# MB_rpi_sys.net
KiCad netlist of a schematic drawn in Altium Designer
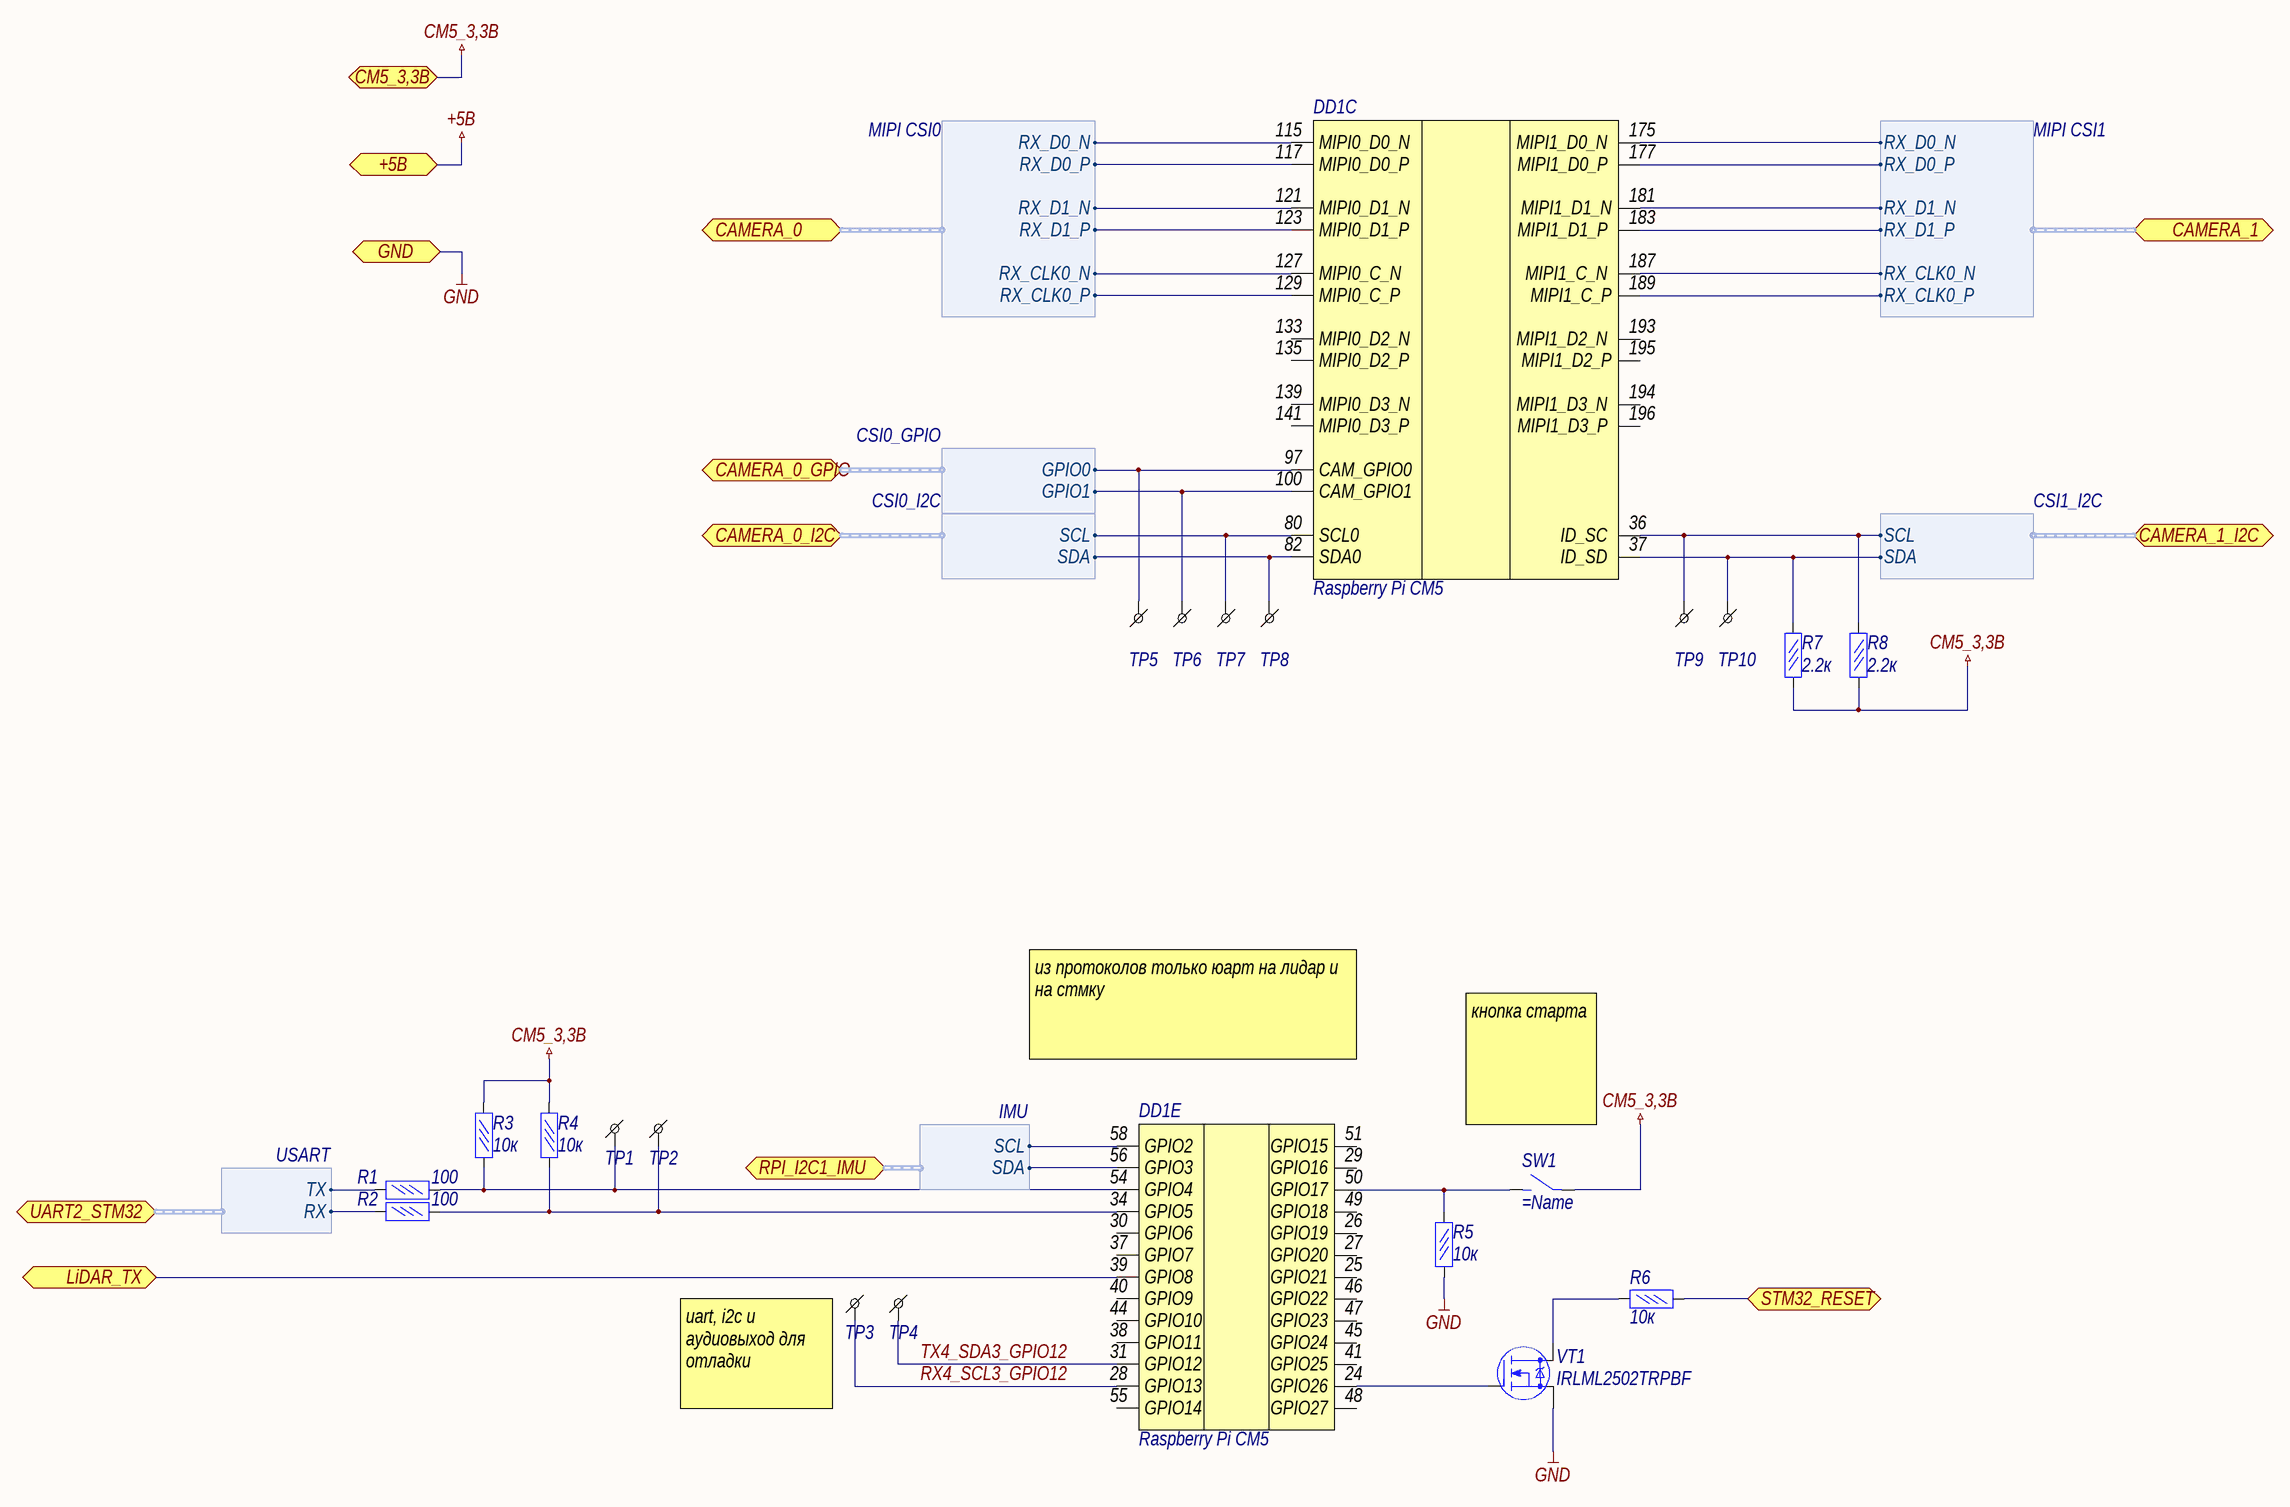
[diagram p0: MB_rpi_sys.SchDoc]

(export (version "E")
  (design (tool "Eeschema 10.0.6"))
  (components
    (comp (ref "DD1")
      (value "Raspberry Pi CM5")
      (footprint "raspberry_pi_compute_module_4_header")
      (description "Raspberry Pi Compute Module 5")
      (libsource (lib "MZBT_SchLibrary") (part "Raspberry Pi CM5"))
    )
    (comp (ref "R1")
      (value "100")
      (footprint "R0402")
      (description "Резистор 0,05Вт")
      (libsource (lib "MZBT_SchLibrary") (part "Резистор 0.05Вт"))
    )
    (comp (ref "R2")
      (value "100")
      (footprint "R0402")
      (description "Резистор 0,05Вт")
      (libsource (lib "MZBT_SchLibrary") (part "Резистор 0.05Вт"))
    )
    (comp (ref "R3")
      (value "10к")
      (footprint "R0402")
      (description "Резистор 0,05Вт")
      (libsource (lib "MZBT_SchLibrary") (part "Резистор 0.05Вт"))
    )
    (comp (ref "R4")
      (value "10к")
      (footprint "R0402")
      (description "Резистор 0,05Вт")
      (libsource (lib "MZBT_SchLibrary") (part "Резистор 0.05Вт"))
    )
    (comp (ref "R5")
      (value "10к")
      (footprint "R0402")
      (description "Резистор 0,05Вт")
      (libsource (lib "") (part "Резистор 0.05Вт_1"))
    )
    (comp (ref "R6")
      (value "10к")
      (footprint "R0402")
      (description "Резистор 0,05Вт")
      (libsource (lib "") (part "Резистор 0.05Вт_2"))
    )
    (comp (ref "R7")
      (value "2.2к")
      (footprint "R0402")
      (description "Резистор 0,05Вт")
      (libsource (lib "") (part "Резистор 0.05Вт_1"))
    )
    (comp (ref "R8")
      (value "2.2к")
      (footprint "R0402")
      (description "Резистор 0,05Вт")
      (libsource (lib "") (part "Резистор 0.05Вт_1"))
    )
    (comp (ref "SW1") (value "~") (footprint "KTD0621") (libsource (lib "MZBT_SchLibrary") (part "button")))
    (comp (ref "TP1")
      (value "TestPoint")
      (footprint "0.5 x 0,9_round")
      (libsource (lib "MZBT_SchLibrary") (part "TestPoint"))
    )
    (comp (ref "TP2")
      (value "TestPoint")
      (footprint "0.5 x 0,9_round")
      (libsource (lib "MZBT_SchLibrary") (part "TestPoint"))
    )
    (comp (ref "TP3")
      (value "TestPoint")
      (footprint "0.5 x 0,9_round")
      (libsource (lib "MZBT_SchLibrary") (part "TestPoint"))
    )
    (comp (ref "TP4")
      (value "TestPoint")
      (footprint "0.5 x 0,9_round")
      (libsource (lib "MZBT_SchLibrary") (part "TestPoint"))
    )
    (comp (ref "TP5")
      (value "TestPoint")
      (footprint "0.5 x 0,9_round")
      (libsource (lib "MZBT_SchLibrary") (part "TestPoint"))
    )
    (comp (ref "TP6")
      (value "TestPoint")
      (footprint "0.5 x 0,9_round")
      (libsource (lib "MZBT_SchLibrary") (part "TestPoint"))
    )
    (comp (ref "TP7")
      (value "TestPoint")
      (footprint "0.5 x 0,9_round")
      (libsource (lib "MZBT_SchLibrary") (part "TestPoint"))
    )
    (comp (ref "TP8")
      (value "TestPoint")
      (footprint "0.5 x 0,9_round")
      (libsource (lib "MZBT_SchLibrary") (part "TestPoint"))
    )
    (comp (ref "TP9")
      (value "TestPoint")
      (footprint "0.5 x 0,9_round")
      (libsource (lib "MZBT_SchLibrary") (part "TestPoint"))
    )
    (comp (ref "TP10")
      (value "TestPoint")
      (footprint "0.5 x 0,9_round")
      (libsource (lib "MZBT_SchLibrary") (part "TestPoint"))
    )
    (comp (ref "VT1")
      (value "IRLML2502TRPBF")
      (footprint "SOT23")
      (description "мосфет n-канал IRLML2502TRPBF")
      (libsource (lib "MZBT_SchLibrary") (part "IRLML2502TRPBF"))
    )
  )
  (nets
    (net (code "10") (name "/GPIO0") (class "Default")
      (node (ref "DD1") (pin "97") (pinfunction "CAM_GPIO0_97") (pintype "passive"))
      (node (ref "TP5") (pin "1") (pinfunction "1_1") (pintype "passive"))
    )
    (net (code "11") (name "/GPIO1") (class "Default")
      (node (ref "DD1") (pin "100") (pinfunction "CAM_GPIO1_100") (pintype "passive"))
      (node (ref "TP6") (pin "1") (pinfunction "1_1") (pintype "passive"))
    )
    (net (code "12") (name "/LiDAR_TX") (class "Default")
      (node (ref "DD1") (pin "39") (pinfunction "GPIO8_39") (pintype "passive"))
    )
    (net (code "13") (name "/RX") (class "Default")
      (node (ref "R2") (pin "1") (pinfunction "1_1") (pintype "passive"))
    )
    (net (code "14") (name "/RX4_SCL3_GPIO12") (class "Default")
      (node (ref "DD1") (pin "28") (pinfunction "GPIO13_28") (pintype "passive"))
      (node (ref "TP3") (pin "1") (pinfunction "1_1") (pintype "passive"))
    )
    (net (code "15") (name "/STM32_RESET") (class "Default")
      (node (ref "R6") (pin "1") (pinfunction "1_1") (pintype "passive"))
    )
    (net (code "16") (name "/TX") (class "Default")
      (node (ref "R1") (pin "1") (pinfunction "1_1") (pintype "passive"))
    )
    (net (code "17") (name "/TX4_SDA3_GPIO12") (class "Default")
      (node (ref "DD1") (pin "31") (pinfunction "GPIO12_31") (pintype "passive"))
      (node (ref "TP4") (pin "1") (pinfunction "1_1") (pintype "passive"))
    )
    (net (code "25") (name "CM5_3,3В") (class "Default")
      (node (ref "R3") (pin "2") (pinfunction "2_2") (pintype "passive"))
      (node (ref "R4") (pin "2") (pinfunction "2_2") (pintype "passive"))
      (node (ref "R7") (pin "1") (pinfunction "1_1") (pintype "passive"))
      (node (ref "R8") (pin "1") (pinfunction "1_1") (pintype "passive"))
      (node (ref "SW1") (pin "1") (pinfunction "1_1") (pintype "passive"))
    )
    (net (code "26") (name "GND") (class "Default")
      (node (ref "R5") (pin "1") (pinfunction "1_1") (pintype "passive"))
      (node (ref "VT1") (pin "2") (pinfunction "S_2") (pintype "passive"))
    )
    (net (code "27") (name "Net-(DD1C-ID_SC)") (class "Default")
      (node (ref "DD1") (pin "36") (pinfunction "ID_SC_36") (pintype "passive"))
      (node (ref "R8") (pin "2") (pinfunction "2_2") (pintype "passive"))
      (node (ref "TP9") (pin "1") (pinfunction "1_1") (pintype "passive"))
    )
    (net (code "28") (name "Net-(DD1C-ID_SD)") (class "Default")
      (node (ref "DD1") (pin "37") (pinfunction "ID_SD_37") (pintype "passive"))
      (node (ref "R7") (pin "2") (pinfunction "2_2") (pintype "passive"))
      (node (ref "TP10") (pin "1") (pinfunction "1_1") (pintype "passive"))
    )
    (net (code "29") (name "Net-(DD1C-SCL0)") (class "Default")
      (node (ref "DD1") (pin "80") (pinfunction "SCL0_80") (pintype "passive"))
      (node (ref "TP7") (pin "1") (pinfunction "1_1") (pintype "passive"))
    )
    (net (code "30") (name "Net-(DD1C-SDA0)") (class "Default")
      (node (ref "DD1") (pin "82") (pinfunction "SDA0_82") (pintype "passive"))
      (node (ref "TP8") (pin "1") (pinfunction "1_1") (pintype "passive"))
    )
    (net (code "31") (name "Net-(DD1E-GPIO4)") (class "Default")
      (node (ref "DD1") (pin "54") (pinfunction "GPIO4_54") (pintype "passive"))
      (node (ref "R1") (pin "2") (pinfunction "2_2") (pintype "passive"))
      (node (ref "R3") (pin "1") (pinfunction "1_1") (pintype "passive"))
      (node (ref "TP1") (pin "1") (pinfunction "1_1") (pintype "passive"))
    )
    (net (code "32") (name "Net-(DD1E-GPIO5)") (class "Default")
      (node (ref "DD1") (pin "34") (pinfunction "GPIO5_34") (pintype "passive"))
      (node (ref "R2") (pin "2") (pinfunction "2_2") (pintype "passive"))
      (node (ref "R4") (pin "1") (pinfunction "1_1") (pintype "passive"))
      (node (ref "TP2") (pin "1") (pinfunction "1_1") (pintype "passive"))
    )
    (net (code "33") (name "Net-(DD1E-GPIO17)") (class "Default")
      (node (ref "DD1") (pin "50") (pinfunction "GPIO17_50") (pintype "passive"))
      (node (ref "R5") (pin "2") (pinfunction "2_2") (pintype "passive"))
      (node (ref "SW1") (pin "2") (pinfunction "2_2") (pintype "passive"))
    )
    (net (code "34") (name "Net-(DD1E-GPIO26)") (class "Default")
      (node (ref "DD1") (pin "24") (pinfunction "GPIO26_24") (pintype "passive"))
      (node (ref "VT1") (pin "1") (pinfunction "G_1") (pintype "passive"))
    )
    (net (code "35") (name "Net-(VT1-D)") (class "Default")
      (node (ref "R6") (pin "2") (pinfunction "2_2") (pintype "passive"))
      (node (ref "VT1") (pin "3") (pinfunction "D_3") (pintype "passive"))
    )
    (net (code "36") (name "unconnected-(DD1C-MIPI0_C_N-Pad127)") (class "Default")
      (node (ref "DD1") (pin "127") (pinfunction "MIPI0_C_N_127") (pintype "passive"))
    )
    (net (code "37") (name "unconnected-(DD1C-MIPI0_C_P-Pad129)") (class "Default")
      (node (ref "DD1") (pin "129") (pinfunction "MIPI0_C_P_129") (pintype "passive"))
    )
    (net (code "38") (name "unconnected-(DD1C-MIPI0_D0_N-Pad115)") (class "Default")
      (node (ref "DD1") (pin "115") (pinfunction "MIPI0_D0_N_115") (pintype "passive"))
    )
    (net (code "39") (name "unconnected-(DD1C-MIPI0_D0_P-Pad117)") (class "Default")
      (node (ref "DD1") (pin "117") (pinfunction "MIPI0_D0_P_117") (pintype "passive"))
    )
    (net (code "40") (name "unconnected-(DD1C-MIPI0_D1_N-Pad121)") (class "Default")
      (node (ref "DD1") (pin "121") (pinfunction "MIPI0_D1_N_121") (pintype "passive"))
    )
    (net (code "41") (name "unconnected-(DD1C-MIPI0_D1_P-Pad123)") (class "Default")
      (node (ref "DD1") (pin "123") (pinfunction "MIPI0_D1_P_123") (pintype "passive"))
    )
    (net (code "42") (name "unconnected-(DD1C-MIPI0_D2_N-Pad133)") (class "Default")
      (node (ref "DD1") (pin "133") (pinfunction "MIPI0_D2_N_133") (pintype "passive"))
    )
    (net (code "43") (name "unconnected-(DD1C-MIPI0_D2_P-Pad135)") (class "Default")
      (node (ref "DD1") (pin "135") (pinfunction "MIPI0_D2_P_135") (pintype "passive"))
    )
    (net (code "44") (name "unconnected-(DD1C-MIPI0_D3_N-Pad139)") (class "Default")
      (node (ref "DD1") (pin "139") (pinfunction "MIPI0_D3_N_139") (pintype "passive"))
    )
    (net (code "45") (name "unconnected-(DD1C-MIPI0_D3_P-Pad141)") (class "Default")
      (node (ref "DD1") (pin "141") (pinfunction "MIPI0_D3_P_141") (pintype "passive"))
    )
    (net (code "46") (name "unconnected-(DD1C-MIPI1_C_P-Pad189)") (class "Default")
      (node (ref "DD1") (pin "189") (pinfunction "MIPI1_C_P_189") (pintype "passive"))
    )
    (net (code "47") (name "unconnected-(DD1C-MIPI1_D0_N-Pad175)") (class "Default")
      (node (ref "DD1") (pin "175") (pinfunction "MIPI1_D0_N_175") (pintype "passive"))
    )
    (net (code "48") (name "unconnected-(DD1C-MIPI1_D0_P-Pad177)") (class "Default")
      (node (ref "DD1") (pin "177") (pinfunction "MIPI1_D0_P_177") (pintype "passive"))
    )
    (net (code "49") (name "unconnected-(DD1C-MIPI1_D1_N-Pad181)") (class "Default")
      (node (ref "DD1") (pin "181") (pinfunction "MIPI1_D1_N_181") (pintype "passive"))
    )
    (net (code "50") (name "unconnected-(DD1C-MIPI1_D1_P-Pad183)") (class "Default")
      (node (ref "DD1") (pin "183") (pinfunction "MIPI1_D1_P_183") (pintype "passive"))
    )
    (net (code "51") (name "unconnected-(DD1C-MIPI1_D2_N-Pad193)") (class "Default")
      (node (ref "DD1") (pin "193") (pinfunction "MIPI1_D2_N_193") (pintype "passive"))
    )
    (net (code "52") (name "unconnected-(DD1C-MIPI1_D2_P-Pad195)") (class "Default")
      (node (ref "DD1") (pin "195") (pinfunction "MIPI1_D2_P_195") (pintype "passive"))
    )
    (net (code "53") (name "unconnected-(DD1C-MIPI1_D3_N-Pad194)") (class "Default")
      (node (ref "DD1") (pin "194") (pinfunction "MIPI1_D3_N_194") (pintype "passive"))
    )
    (net (code "54") (name "unconnected-(DD1C-MIPI1_D3_P-Pad196)") (class "Default")
      (node (ref "DD1") (pin "196") (pinfunction "MIPI1_D3_P_196") (pintype "passive"))
    )
    (net (code "55") (name "unconnected-(DD1C-_MIPI1_C_N-Pad187)") (class "Default")
      (node (ref "DD1") (pin "187") (pinfunction "_MIPI1_C_N_187") (pintype "passive"))
    )
    (net (code "56") (name "unconnected-(DD1E-GPIO2-Pad58)") (class "Default")
      (node (ref "DD1") (pin "58") (pinfunction "GPIO2_58") (pintype "passive"))
    )
    (net (code "57") (name "unconnected-(DD1E-GPIO3-Pad56)") (class "Default")
      (node (ref "DD1") (pin "56") (pinfunction "GPIO3_56") (pintype "passive"))
    )
    (net (code "58") (name "unconnected-(DD1E-GPIO6-Pad30)") (class "Default")
      (node (ref "DD1") (pin "30") (pinfunction "GPIO6_30") (pintype "passive"))
    )
    (net (code "59") (name "unconnected-(DD1E-GPIO7-Pad37)") (class "Default")
      (node (ref "DD1") (pin "37") (pinfunction "GPIO7_37") (pintype "passive"))
    )
    (net (code "60") (name "unconnected-(DD1E-GPIO9-Pad40)") (class "Default")
      (node (ref "DD1") (pin "40") (pinfunction "GPIO9_40") (pintype "passive"))
    )
    (net (code "61") (name "unconnected-(DD1E-GPIO10-Pad44)") (class "Default")
      (node (ref "DD1") (pin "44") (pinfunction "GPIO10_44") (pintype "passive"))
    )
    (net (code "62") (name "unconnected-(DD1E-GPIO11-Pad38)") (class "Default")
      (node (ref "DD1") (pin "38") (pinfunction "GPIO11_38") (pintype "passive"))
    )
    (net (code "63") (name "unconnected-(DD1E-GPIO14-Pad55)") (class "Default")
      (node (ref "DD1") (pin "55") (pinfunction "GPIO14_55") (pintype "passive"))
    )
    (net (code "64") (name "unconnected-(DD1E-GPIO15-Pad51)") (class "Default")
      (node (ref "DD1") (pin "51") (pinfunction "GPIO15_51") (pintype "passive"))
    )
    (net (code "65") (name "unconnected-(DD1E-GPIO16-Pad29)") (class "Default")
      (node (ref "DD1") (pin "29") (pinfunction "GPIO16_29") (pintype "passive"))
    )
    (net (code "66") (name "unconnected-(DD1E-GPIO18-Pad49)") (class "Default")
      (node (ref "DD1") (pin "49") (pinfunction "GPIO18_49") (pintype "passive"))
    )
    (net (code "67") (name "unconnected-(DD1E-GPIO19-Pad26)") (class "Default")
      (node (ref "DD1") (pin "26") (pinfunction "GPIO19_26") (pintype "passive"))
    )
    (net (code "68") (name "unconnected-(DD1E-GPIO20-Pad27)") (class "Default")
      (node (ref "DD1") (pin "27") (pinfunction "GPIO20_27") (pintype "passive"))
    )
    (net (code "69") (name "unconnected-(DD1E-GPIO21-Pad25)") (class "Default")
      (node (ref "DD1") (pin "25") (pinfunction "GPIO21_25") (pintype "passive"))
    )
    (net (code "70") (name "unconnected-(DD1E-GPIO22-Pad46)") (class "Default")
      (node (ref "DD1") (pin "46") (pinfunction "GPIO22_46") (pintype "passive"))
    )
    (net (code "71") (name "unconnected-(DD1E-GPIO23-Pad47)") (class "Default")
      (node (ref "DD1") (pin "47") (pinfunction "GPIO23_47") (pintype "passive"))
    )
    (net (code "72") (name "unconnected-(DD1E-GPIO24-Pad45)") (class "Default")
      (node (ref "DD1") (pin "45") (pinfunction "GPIO24_45") (pintype "passive"))
    )
    (net (code "73") (name "unconnected-(DD1E-GPIO25-Pad41)") (class "Default")
      (node (ref "DD1") (pin "41") (pinfunction "GPIO25_41") (pintype "passive"))
    )
    (net (code "74") (name "unconnected-(DD1E-GPIO27-Pad48)") (class "Default")
      (node (ref "DD1") (pin "48") (pinfunction "GPIO27_48") (pintype "passive"))
    )
  )
)
